# Qwiic_Adaptive_Switch_Single.net
KiCad netlist of a schematic drawn in EAGLE
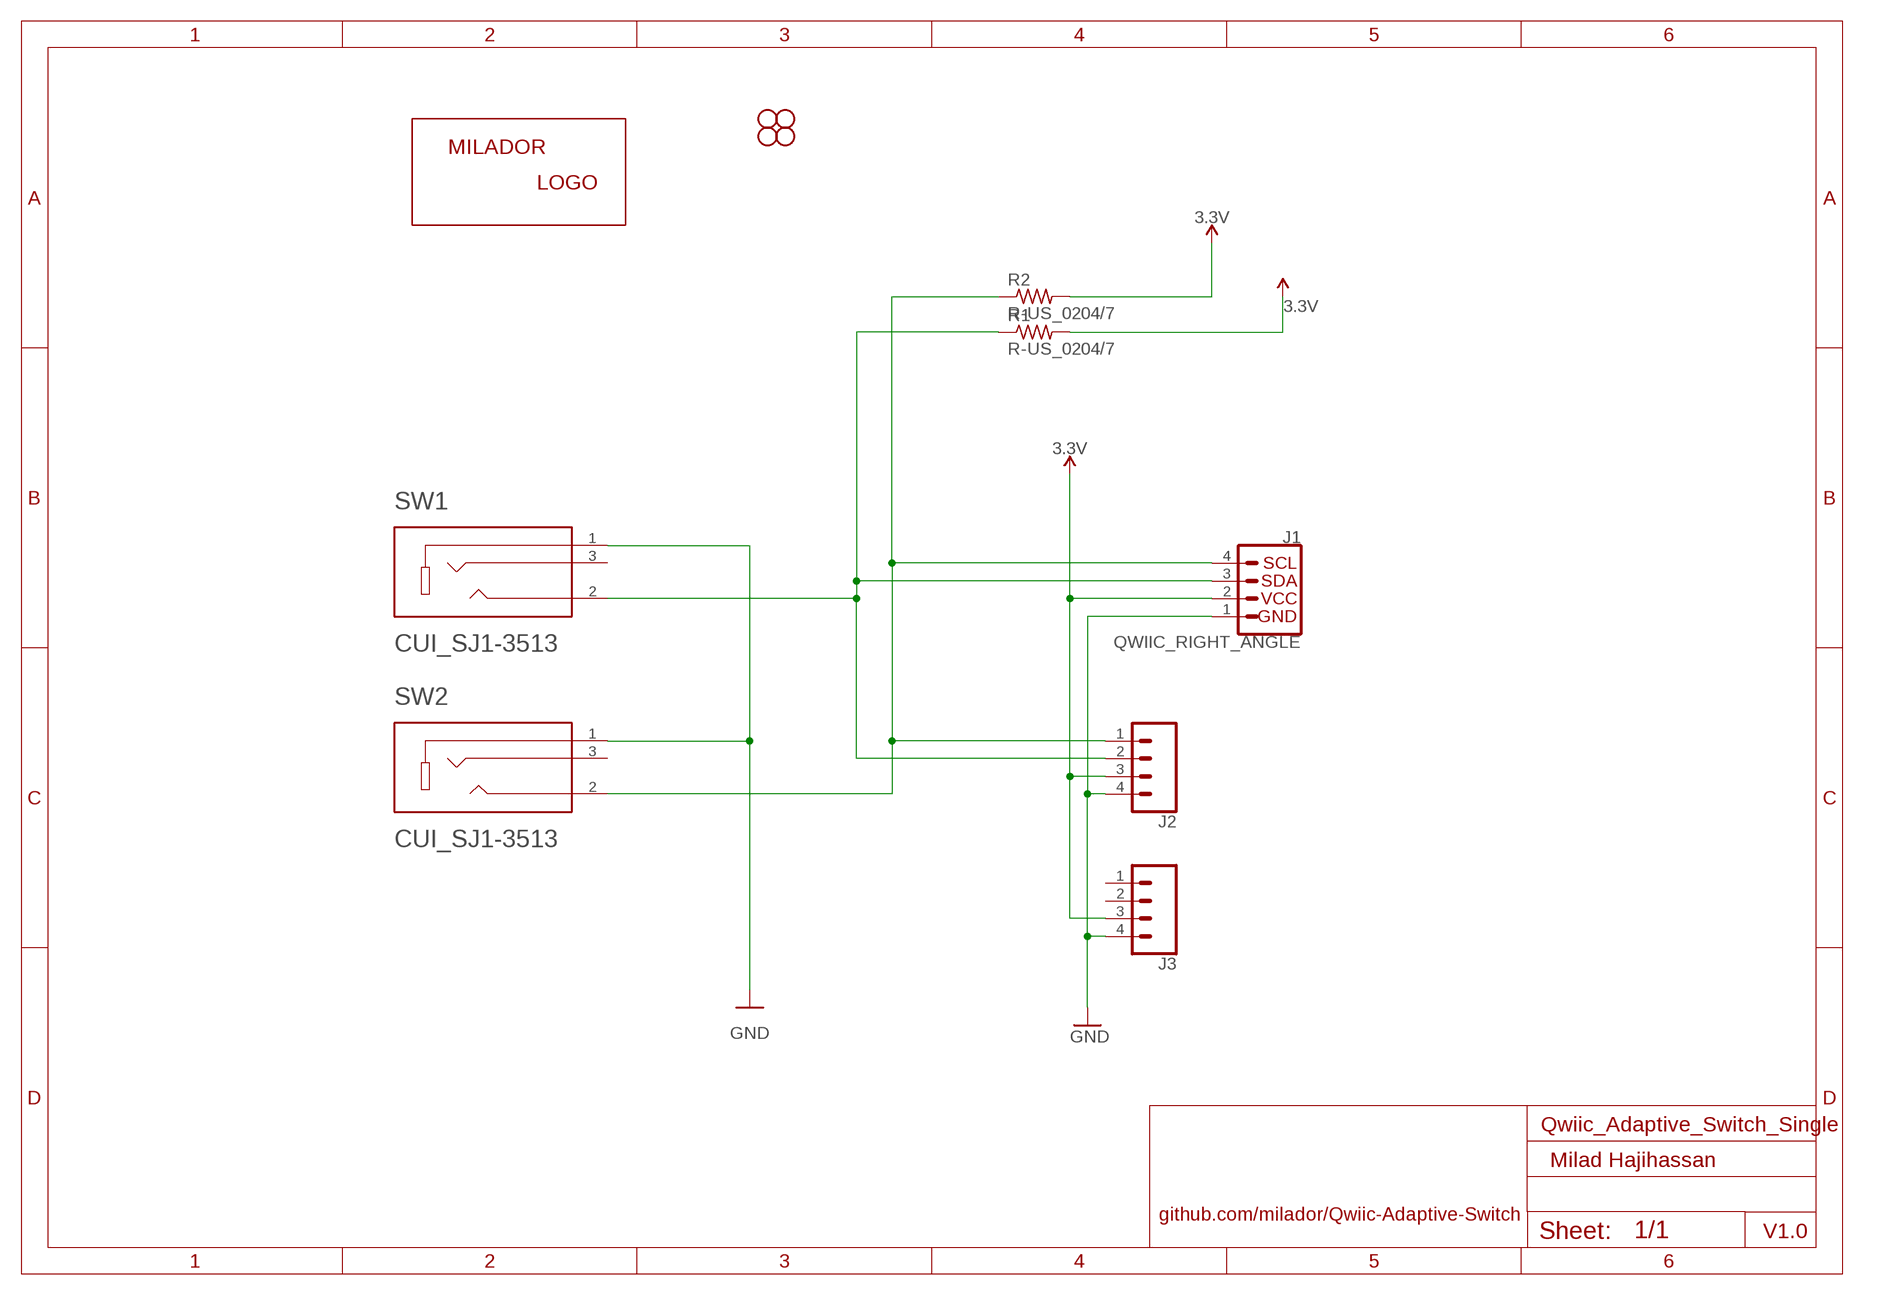
[diagram p0: schematic, sheet 1]

(export (version "E")
  (design (tool "Eeschema 10.0.6"))
  (components
    (comp (ref "J1")
      (value "QWIIC_RIGHT_ANGLE")
      (footprint "eagle-import:CONNECTORS_JST04_1MM_RA")
      (libsource (lib "eagle-import") (part "QWIIC_CONNECTORSJS-1MM"))
    )
    (comp (ref "J2")
      (value "J2")
      (footprint "eagle-import:CONNECTORS_1X04_NO_SILK")
      (libsource (lib "eagle-import") (part "CONNECTORS_CONN_041X04_NO_SILK"))
    )
    (comp (ref "J3")
      (value "CONNECTORS_CONN_041X04_NO_SILK")
      (footprint "eagle-import:CONNECTORS_1X04_NO_SILK")
      (libsource (lib "eagle-import") (part "CONNECTORS_CONN_041X04_NO_SILK"))
    )
    (comp (ref "JP1")
      (value "STAND-OFF")
      (footprint "eagle-import:STAND-OFF")
      (libsource (lib "eagle-import") (part "SparkFun-Hardware_519_STAND-OFF"))
    )
    (comp (ref "JP2")
      (value "STAND-OFF")
      (footprint "eagle-import:STAND-OFF")
      (libsource (lib "eagle-import") (part "STAND-OFF"))
    )
    (comp (ref "JP3")
      (value "STAND-OFF")
      (footprint "eagle-import:STAND-OFF")
      (libsource (lib "eagle-import") (part "STAND-OFF"))
    )
    (comp (ref "JP4")
      (value "STAND-OFF")
      (footprint "eagle-import:STAND-OFF")
      (libsource (lib "eagle-import") (part "STAND-OFF"))
    )
    (comp (ref "R1")
      (value "R-US_0204/7")
      (footprint "eagle-import:0204_7")
      (libsource (lib "eagle-import") (part "R-US_0204/7"))
    )
    (comp (ref "R2")
      (value "R-US_0204/7")
      (footprint "eagle-import:0204_7")
      (libsource (lib "eagle-import") (part "R-US_0204/7"))
    )
    (comp (ref "SW1")
      (value "CUI_SJ1-3513")
      (footprint "eagle-import:CUI_SJ1-3513")
      (libsource (lib "eagle-import") (part "CUI_SJ1-3513"))
    )
    (comp (ref "SW2")
      (value "CUI_SJ1-3513")
      (footprint "eagle-import:CUI_SJ1-3513")
      (libsource (lib "eagle-import") (part "CUI_SJ1-3513"))
    )
    (comp (ref "U$2")
      (value "MILADOR-LOGO-")
      (footprint "eagle-import:MILADOR_LOGO1")
      (libsource (lib "eagle-import") (part "MILADOR-LOGO-"))
    )
  )
  (nets
    (net (code "1") (name "3.3V") (class "Default")
      (node (ref "J1") (pin "2") (pinfunction "2_2") (pintype "power_in"))
      (node (ref "J2") (pin "3") (pinfunction "3_3") (pintype "passive"))
      (node (ref "J3") (pin "3") (pinfunction "3_3") (pintype "passive"))
      (node (ref "R1") (pin "2") (pinfunction "2_2") (pintype "passive"))
      (node (ref "R2") (pin "2") (pinfunction "2_2") (pintype "passive"))
    )
    (net (code "2") (name "GND") (class "Default")
      (node (ref "J1") (pin "1") (pinfunction "1_1") (pintype "power_in"))
      (node (ref "J2") (pin "4") (pinfunction "4_4") (pintype "passive"))
      (node (ref "J3") (pin "4") (pinfunction "4_4") (pintype "passive"))
      (node (ref "SW1") (pin "1") (pinfunction "1_1") (pintype "passive"))
      (node (ref "SW2") (pin "1") (pinfunction "1_1") (pintype "passive"))
    )
    (net (code "3") (name "Net-(J1-Pad3)") (class "Default")
      (node (ref "J1") (pin "3") (pinfunction "3_3") (pintype "passive"))
      (node (ref "J2") (pin "2") (pinfunction "2_2") (pintype "passive"))
      (node (ref "R1") (pin "1") (pinfunction "1_1") (pintype "passive"))
      (node (ref "SW1") (pin "2") (pinfunction "2_2") (pintype "passive"))
    )
    (net (code "4") (name "Net-(J1-Pad4)") (class "Default")
      (node (ref "J1") (pin "4") (pinfunction "4_4") (pintype "passive"))
      (node (ref "J2") (pin "1") (pinfunction "1_1") (pintype "passive"))
      (node (ref "R2") (pin "1") (pinfunction "1_1") (pintype "passive"))
      (node (ref "SW2") (pin "2") (pinfunction "2_2") (pintype "passive"))
    )
    (net (code "5") (name "unconnected-(J3-Pad1)") (class "Default")
      (node (ref "J3") (pin "1") (pinfunction "1_1") (pintype "passive"))
    )
    (net (code "6") (name "unconnected-(J3-Pad2)") (class "Default")
      (node (ref "J3") (pin "2") (pinfunction "2_2") (pintype "passive"))
    )
    (net (code "7") (name "unconnected-(SW1-Pad3)") (class "Default")
      (node (ref "SW1") (pin "3") (pinfunction "3_3") (pintype "passive"))
    )
    (net (code "8") (name "unconnected-(SW2-Pad3)") (class "Default")
      (node (ref "SW2") (pin "3") (pinfunction "3_3") (pintype "passive"))
    )
  )
)
